# w550io_Teensy_DMX.net
KiCad netlist of a schematic drawn in EAGLE
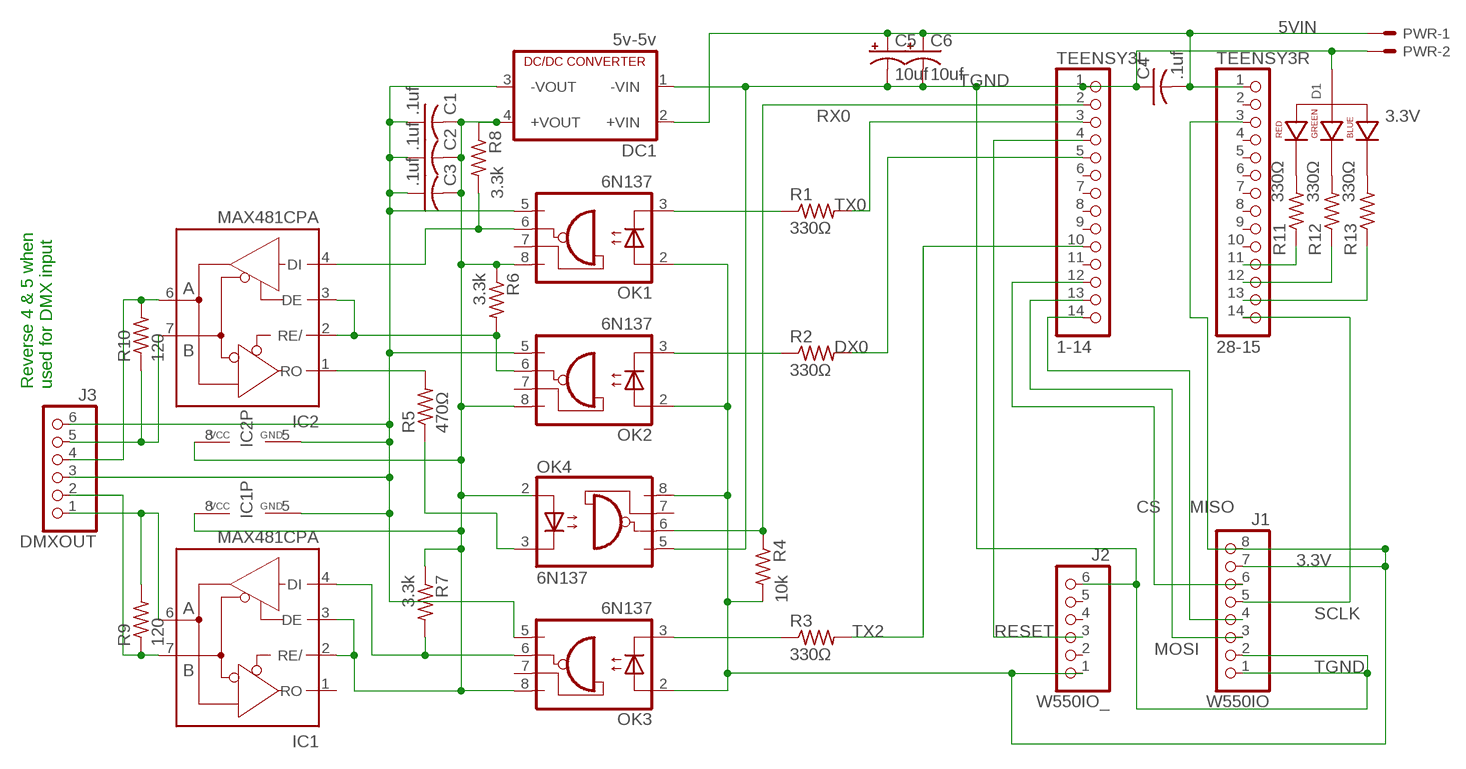
[diagram p0: schematic, sheet 1]

(export (version "E")
  (design (tool "Eeschema 10.0.6"))
  (components
    (comp (ref "C1")
      (value ".1uf")
      (footprint "eagle-import:C050-024X044")
      (libsource (lib "eagle-import") (part "C-US050-024X044"))
    )
    (comp (ref "C2")
      (value ".1uf")
      (footprint "eagle-import:C050-024X044")
      (libsource (lib "eagle-import") (part "C-US050-024X044"))
    )
    (comp (ref "C3")
      (value ".1uf")
      (footprint "eagle-import:C050-024X044")
      (libsource (lib "eagle-import") (part "C-US050-024X044"))
    )
    (comp (ref "C4")
      (value ".1uf")
      (footprint "eagle-import:C050-024X044")
      (libsource (lib "eagle-import") (part "C-US050-024X044"))
    )
    (comp (ref "C5")
      (value "10uf")
      (footprint "eagle-import:B45181B")
      (libsource (lib "eagle-import") (part "CPOL-USB45181B"))
    )
    (comp (ref "C6")
      (value "10uf")
      (footprint "eagle-import:B45181B")
      (libsource (lib "eagle-import") (part "CPOL-USB45181B"))
    )
    (comp (ref "D1")
      (value "LED-RGB-CA-THRUCLEAR")
      (footprint "eagle-import:LED-RGB-THRU")
      (libsource (lib "eagle-import") (part "LED-RGB-CA-THRUCLEAR"))
    )
    (comp (ref "DC1")
      (value "5v-5v")
      (footprint "eagle-import:NME")
      (fields (field (name "MF") "C & D TECHNOLOGIES, INC") (field (name "MPN") "NME1205D"))
      (libsource (lib "eagle-import") (part "NME"))
    )
    (comp (ref "DMXOUT")
      (value "J3")
      (footprint "eagle-import:1X06-BIG")
      (libsource (lib "eagle-import") (part "PINHD-1X6B"))
    )
    (comp (ref "IC1")
      (value "MAX481CPA")
      (footprint "eagle-import:DIL08")
      (fields (field (name "MPN") "MAX481CPA+"))
      (libsource (lib "eagle-import") (part "MAX481CPA"))
    )
    (comp (ref "IC2")
      (value "MAX481CPA")
      (footprint "eagle-import:DIL08")
      (fields (field (name "MPN") "MAX481CPA+"))
      (libsource (lib "eagle-import") (part "MAX481CPA"))
    )
    (comp (ref "OK1")
      (value "6N137")
      (footprint "eagle-import:DIL08")
      (libsource (lib "eagle-import") (part "6N137"))
    )
    (comp (ref "OK2")
      (value "6N137")
      (footprint "eagle-import:DIL08")
      (libsource (lib "eagle-import") (part "6N137"))
    )
    (comp (ref "OK3")
      (value "6N137")
      (footprint "eagle-import:DIL08")
      (libsource (lib "eagle-import") (part "6N137"))
    )
    (comp (ref "OK4")
      (value "6N137")
      (footprint "eagle-import:DIL08")
      (libsource (lib "eagle-import") (part "6N137"))
    )
    (comp (ref "PWR")
      (value "22-23-2021")
      (footprint "eagle-import:22-23-2021")
      (fields (field (name "MF") "MOLEX"))
      (libsource (lib "eagle-import") (part "22-23-2021"))
    )
    (comp (ref "R1")
      (value "330Ω")
      (footprint "eagle-import:0204_5")
      (libsource (lib "eagle-import") (part "R-US_0204/5"))
    )
    (comp (ref "R2")
      (value "330Ω")
      (footprint "eagle-import:0204_5")
      (libsource (lib "eagle-import") (part "R-US_0204/5"))
    )
    (comp (ref "R3")
      (value "330Ω")
      (footprint "eagle-import:0204_5")
      (libsource (lib "eagle-import") (part "R-US_0204/5"))
    )
    (comp (ref "R4")
      (value "10k")
      (footprint "eagle-import:0204_5")
      (libsource (lib "eagle-import") (part "R-US_0204/5"))
    )
    (comp (ref "R5")
      (value "470Ω")
      (footprint "eagle-import:0204_5")
      (libsource (lib "eagle-import") (part "R-US_0204/5"))
    )
    (comp (ref "R6")
      (value "3.3k")
      (footprint "eagle-import:0204_5")
      (libsource (lib "eagle-import") (part "R-US_0204/5"))
    )
    (comp (ref "R7")
      (value "3.3k")
      (footprint "eagle-import:0204_5")
      (libsource (lib "eagle-import") (part "R-US_0204/5"))
    )
    (comp (ref "R8")
      (value "3.3k")
      (footprint "eagle-import:0204_5")
      (libsource (lib "eagle-import") (part "R-US_0204/5"))
    )
    (comp (ref "R9")
      (value "120")
      (footprint "eagle-import:0204_5")
      (libsource (lib "eagle-import") (part "R-US_0204/5"))
    )
    (comp (ref "R10")
      (value "120")
      (footprint "eagle-import:0204_5")
      (libsource (lib "eagle-import") (part "R-US_0204/5"))
    )
    (comp (ref "R11")
      (value "330Ω")
      (footprint "eagle-import:0204_5")
      (libsource (lib "eagle-import") (part "R-US_0204/5"))
    )
    (comp (ref "R12")
      (value "330Ω")
      (footprint "eagle-import:0204_5")
      (libsource (lib "eagle-import") (part "R-US_0204/5"))
    )
    (comp (ref "R13")
      (value "330Ω")
      (footprint "eagle-import:0204_5")
      (libsource (lib "eagle-import") (part "R-US_0204/5"))
    )
    (comp (ref "TEENSY3L")
      (value "1-14")
      (footprint "eagle-import:1X14")
      (libsource (lib "eagle-import") (part "PINHD-1X14"))
    )
    (comp (ref "TEENSY3R")
      (value "28-15")
      (footprint "eagle-import:1X14")
      (libsource (lib "eagle-import") (part "PINHD-1X14"))
    )
    (comp (ref "W550IO")
      (value "J1")
      (footprint "eagle-import:1X08-BIG")
      (libsource (lib "eagle-import") (part "PINHD-1X8BIG"))
    )
    (comp (ref "W550IO_")
      (value "J2")
      (footprint "eagle-import:1X06-BIG")
      (libsource (lib "eagle-import") (part "PINHD-1X6B"))
    )
  )
  (nets
    (net (code "1") (name "/3.3V") (class "Default")
      (node (ref "OK1") (pin "2") (pinfunction "A_2") (pintype "passive"))
      (node (ref "OK2") (pin "2") (pinfunction "A_2") (pintype "passive"))
      (node (ref "OK3") (pin "2") (pinfunction "A_2") (pintype "passive"))
      (node (ref "OK4") (pin "8") (pinfunction "VCC_8") (pintype "passive"))
      (node (ref "R4") (pin "2") (pinfunction "2_2") (pintype "passive"))
      (node (ref "TEENSY3R") (pin "3") (pinfunction "3_3") (pintype "passive"))
      (node (ref "W550IO") (pin "7") (pinfunction "7_7") (pintype "passive"))
      (node (ref "W550IO") (pin "8") (pinfunction "8_8") (pintype "passive"))
      (node (ref "W550IO_") (pin "1") (pinfunction "1_1") (pintype "passive"))
    )
    (net (code "2") (name "/5VIN") (class "Default")
      (node (ref "C4") (pin "2") (pinfunction "2_2") (pintype "passive"))
      (node (ref "C5") (pin "+") (pinfunction "+_+") (pintype "passive"))
      (node (ref "C6") (pin "+") (pinfunction "+_+") (pintype "passive"))
      (node (ref "DC1") (pin "2") (pinfunction "+VIN_2") (pintype "passive"))
      (node (ref "PWR") (pin "1") (pinfunction "S_1") (pintype "passive"))
      (node (ref "TEENSY3R") (pin "1") (pinfunction "1_1") (pintype "passive"))
    )
    (net (code "3") (name "/CS") (class "Default")
      (node (ref "TEENSY3L") (pin "12") (pinfunction "12_12") (pintype "passive"))
      (node (ref "W550IO") (pin "6") (pinfunction "6_6") (pintype "passive"))
    )
    (net (code "4") (name "/DX0") (class "Default")
      (node (ref "R2") (pin "2") (pinfunction "2_2") (pintype "passive"))
      (node (ref "TEENSY3L") (pin "5") (pinfunction "5_5") (pintype "passive"))
    )
    (net (code "5") (name "/MISO") (class "Default")
      (node (ref "TEENSY3L") (pin "14") (pinfunction "14_14") (pintype "passive"))
      (node (ref "W550IO") (pin "4") (pinfunction "4_4") (pintype "passive"))
    )
    (net (code "6") (name "/MOSI") (class "Default")
      (node (ref "TEENSY3L") (pin "13") (pinfunction "13_13") (pintype "passive"))
      (node (ref "W550IO") (pin "3") (pinfunction "3_3") (pintype "passive"))
    )
    (net (code "7") (name "/RESET") (class "Default")
      (node (ref "TEENSY3L") (pin "4") (pinfunction "4_4") (pintype "passive"))
      (node (ref "W550IO_") (pin "3") (pinfunction "3_3") (pintype "passive"))
    )
    (net (code "8") (name "/RX0") (class "Default")
      (node (ref "OK4") (pin "6") (pinfunction "VO_6") (pintype "passive"))
      (node (ref "R4") (pin "1") (pinfunction "1_1") (pintype "passive"))
      (node (ref "TEENSY3L") (pin "2") (pinfunction "2_2") (pintype "passive"))
    )
    (net (code "9") (name "/SCLK") (class "Default")
      (node (ref "TEENSY3R") (pin "14") (pinfunction "14_14") (pintype "passive"))
      (node (ref "W550IO") (pin "5") (pinfunction "5_5") (pintype "passive"))
    )
    (net (code "10") (name "/TGND") (class "Default")
      (node (ref "C4") (pin "1") (pinfunction "1_1") (pintype "passive"))
      (node (ref "C5") (pin "-") (pinfunction "-_-") (pintype "passive"))
      (node (ref "C6") (pin "-") (pinfunction "-_-") (pintype "passive"))
      (node (ref "D1") (pin "2") (pinfunction "ANODE_2") (pintype "bidirectional"))
      (node (ref "DC1") (pin "1") (pinfunction "-VIN_1") (pintype "passive"))
      (node (ref "OK4") (pin "5") (pinfunction "GND_5") (pintype "passive"))
      (node (ref "PWR") (pin "2") (pinfunction "S_2") (pintype "passive"))
      (node (ref "TEENSY3L") (pin "1") (pinfunction "1_1") (pintype "passive"))
      (node (ref "W550IO") (pin "1") (pinfunction "1_1") (pintype "passive"))
      (node (ref "W550IO") (pin "2") (pinfunction "2_2") (pintype "passive"))
      (node (ref "W550IO_") (pin "6") (pinfunction "6_6") (pintype "passive"))
    )
    (net (code "11") (name "/TX0") (class "Default")
      (node (ref "R1") (pin "2") (pinfunction "2_2") (pintype "passive"))
      (node (ref "TEENSY3L") (pin "3") (pinfunction "3_3") (pintype "passive"))
    )
    (net (code "12") (name "/TX2") (class "Default")
      (node (ref "R3") (pin "2") (pinfunction "2_2") (pintype "passive"))
      (node (ref "TEENSY3L") (pin "10") (pinfunction "10_10") (pintype "passive"))
    )
    (net (code "13") (name "Net-(D1-BLUE_CATHODE)") (class "Default")
      (node (ref "D1") (pin "4") (pinfunction "BLUE_CATHODE_4") (pintype "bidirectional"))
      (node (ref "R13") (pin "2") (pinfunction "2_2") (pintype "passive"))
    )
    (net (code "14") (name "Net-(D1-GREEN_CATHODE)") (class "Default")
      (node (ref "D1") (pin "3") (pinfunction "GREEN_CATHODE_3") (pintype "bidirectional"))
      (node (ref "R12") (pin "2") (pinfunction "2_2") (pintype "passive"))
    )
    (net (code "15") (name "Net-(D1-RED_CATHODE)") (class "Default")
      (node (ref "D1") (pin "1") (pinfunction "RED_CATHODE_1") (pintype "bidirectional"))
      (node (ref "R11") (pin "2") (pinfunction "2_2") (pintype "passive"))
    )
    (net (code "16") (name "Net-(DC1-+VOUT)") (class "Default")
      (node (ref "C1") (pin "2") (pinfunction "2_2") (pintype "passive"))
      (node (ref "C2") (pin "2") (pinfunction "2_2") (pintype "passive"))
      (node (ref "C3") (pin "2") (pinfunction "2_2") (pintype "passive"))
      (node (ref "DC1") (pin "4") (pinfunction "+VOUT_4") (pintype "passive"))
      (node (ref "IC1") (pin "2") (pinfunction "RE/_2") (pintype "input"))
      (node (ref "IC1") (pin "3") (pinfunction "DE_3") (pintype "input"))
      (node (ref "IC1") (pin "8") (pinfunction "VCC_8") (pintype "power_in"))
      (node (ref "IC2") (pin "8") (pinfunction "VCC_8") (pintype "power_in"))
      (node (ref "OK1") (pin "8") (pinfunction "VCC_8") (pintype "passive"))
      (node (ref "OK2") (pin "8") (pinfunction "VCC_8") (pintype "passive"))
      (node (ref "OK3") (pin "8") (pinfunction "VCC_8") (pintype "passive"))
      (node (ref "OK4") (pin "2") (pinfunction "A_2") (pintype "passive"))
      (node (ref "R6") (pin "1") (pinfunction "1_1") (pintype "passive"))
      (node (ref "R7") (pin "1") (pinfunction "1_1") (pintype "passive"))
      (node (ref "R8") (pin "1") (pinfunction "1_1") (pintype "passive"))
    )
    (net (code "17") (name "Net-(DC1--VOUT)") (class "Default")
      (node (ref "C1") (pin "1") (pinfunction "1_1") (pintype "passive"))
      (node (ref "C2") (pin "1") (pinfunction "1_1") (pintype "passive"))
      (node (ref "C3") (pin "1") (pinfunction "1_1") (pintype "passive"))
      (node (ref "DC1") (pin "3") (pinfunction "-VOUT_3") (pintype "passive"))
      (node (ref "DMXOUT") (pin "3") (pinfunction "3_3") (pintype "passive"))
      (node (ref "DMXOUT") (pin "6") (pinfunction "6_6") (pintype "passive"))
      (node (ref "IC1") (pin "5") (pinfunction "GND_5") (pintype "power_in"))
      (node (ref "IC2") (pin "5") (pinfunction "GND_5") (pintype "power_in"))
      (node (ref "OK1") (pin "5") (pinfunction "GND_5") (pintype "passive"))
      (node (ref "OK2") (pin "5") (pinfunction "GND_5") (pintype "passive"))
      (node (ref "OK3") (pin "5") (pinfunction "GND_5") (pintype "passive"))
    )
    (net (code "18") (name "Net-(IC1A-A)") (class "Default")
      (node (ref "DMXOUT") (pin "1") (pinfunction "1_1") (pintype "passive"))
      (node (ref "IC1") (pin "6") (pinfunction "A_6") (pintype "passive"))
      (node (ref "R9") (pin "2") (pinfunction "2_2") (pintype "passive"))
    )
    (net (code "19") (name "Net-(IC1A-B)") (class "Default")
      (node (ref "DMXOUT") (pin "2") (pinfunction "2_2") (pintype "passive"))
      (node (ref "IC1") (pin "7") (pinfunction "B_7") (pintype "passive"))
      (node (ref "R9") (pin "1") (pinfunction "1_1") (pintype "passive"))
    )
    (net (code "20") (name "Net-(IC1A-DI)") (class "Default")
      (node (ref "IC1") (pin "4") (pinfunction "DI_4") (pintype "input"))
      (node (ref "OK3") (pin "6") (pinfunction "VO_6") (pintype "passive"))
      (node (ref "R7") (pin "2") (pinfunction "2_2") (pintype "passive"))
    )
    (net (code "21") (name "Net-(IC2A-A)") (class "Default")
      (node (ref "DMXOUT") (pin "4") (pinfunction "4_4") (pintype "passive"))
      (node (ref "IC2") (pin "6") (pinfunction "A_6") (pintype "passive"))
      (node (ref "R10") (pin "2") (pinfunction "2_2") (pintype "passive"))
    )
    (net (code "22") (name "Net-(IC2A-B)") (class "Default")
      (node (ref "DMXOUT") (pin "5") (pinfunction "5_5") (pintype "passive"))
      (node (ref "IC2") (pin "7") (pinfunction "B_7") (pintype "passive"))
      (node (ref "R10") (pin "1") (pinfunction "1_1") (pintype "passive"))
    )
    (net (code "23") (name "Net-(IC2A-DE)") (class "Default")
      (node (ref "IC2") (pin "2") (pinfunction "RE/_2") (pintype "input"))
      (node (ref "IC2") (pin "3") (pinfunction "DE_3") (pintype "input"))
      (node (ref "OK2") (pin "6") (pinfunction "VO_6") (pintype "passive"))
      (node (ref "R6") (pin "2") (pinfunction "2_2") (pintype "passive"))
    )
    (net (code "24") (name "Net-(IC2A-DI)") (class "Default")
      (node (ref "IC2") (pin "4") (pinfunction "DI_4") (pintype "input"))
      (node (ref "OK1") (pin "6") (pinfunction "VO_6") (pintype "passive"))
      (node (ref "R8") (pin "2") (pinfunction "2_2") (pintype "passive"))
    )
    (net (code "25") (name "Net-(IC2A-RO)") (class "Default")
      (node (ref "IC2") (pin "1") (pinfunction "RO_1") (pintype "output"))
      (node (ref "R5") (pin "2") (pinfunction "2_2") (pintype "passive"))
    )
    (net (code "26") (name "Net-(OK1-C)") (class "Default")
      (node (ref "OK1") (pin "3") (pinfunction "C_3") (pintype "passive"))
      (node (ref "R1") (pin "1") (pinfunction "1_1") (pintype "passive"))
    )
    (net (code "27") (name "Net-(OK2-C)") (class "Default")
      (node (ref "OK2") (pin "3") (pinfunction "C_3") (pintype "passive"))
      (node (ref "R2") (pin "1") (pinfunction "1_1") (pintype "passive"))
    )
    (net (code "28") (name "Net-(OK3-C)") (class "Default")
      (node (ref "OK3") (pin "3") (pinfunction "C_3") (pintype "passive"))
      (node (ref "R3") (pin "1") (pinfunction "1_1") (pintype "passive"))
    )
    (net (code "29") (name "Net-(OK4-C)") (class "Default")
      (node (ref "OK4") (pin "3") (pinfunction "C_3") (pintype "passive"))
      (node (ref "R5") (pin "1") (pinfunction "1_1") (pintype "passive"))
    )
    (net (code "30") (name "Net-(R11-Pad1)") (class "Default")
      (node (ref "R11") (pin "1") (pinfunction "1_1") (pintype "passive"))
      (node (ref "TEENSY3R") (pin "11") (pinfunction "11_11") (pintype "passive"))
    )
    (net (code "31") (name "Net-(R12-Pad1)") (class "Default")
      (node (ref "R12") (pin "1") (pinfunction "1_1") (pintype "passive"))
      (node (ref "TEENSY3R") (pin "12") (pinfunction "12_12") (pintype "passive"))
    )
    (net (code "32") (name "Net-(R13-Pad1)") (class "Default")
      (node (ref "R13") (pin "1") (pinfunction "1_1") (pintype "passive"))
      (node (ref "TEENSY3R") (pin "13") (pinfunction "13_13") (pintype "passive"))
    )
    (net (code "33") (name "unconnected-(IC1A-RO-Pad1)") (class "Default")
      (node (ref "IC1") (pin "1") (pinfunction "RO_1") (pintype "output"))
    )
    (net (code "34") (name "unconnected-(OK1-VE-Pad7)") (class "Default")
      (node (ref "OK1") (pin "7") (pinfunction "VE_7") (pintype "passive"))
    )
    (net (code "35") (name "unconnected-(OK2-VE-Pad7)") (class "Default")
      (node (ref "OK2") (pin "7") (pinfunction "VE_7") (pintype "passive"))
    )
    (net (code "36") (name "unconnected-(OK3-VE-Pad7)") (class "Default")
      (node (ref "OK3") (pin "7") (pinfunction "VE_7") (pintype "passive"))
    )
    (net (code "37") (name "unconnected-(OK4-VE-Pad7)") (class "Default")
      (node (ref "OK4") (pin "7") (pinfunction "VE_7") (pintype "passive"))
    )
    (net (code "38") (name "unconnected-(TEENSY3L-Pad6)") (class "Default")
      (node (ref "TEENSY3L") (pin "6") (pinfunction "6_6") (pintype "passive"))
    )
    (net (code "39") (name "unconnected-(TEENSY3L-Pad7)") (class "Default")
      (node (ref "TEENSY3L") (pin "7") (pinfunction "7_7") (pintype "passive"))
    )
    (net (code "40") (name "unconnected-(TEENSY3L-Pad8)") (class "Default")
      (node (ref "TEENSY3L") (pin "8") (pinfunction "8_8") (pintype "passive"))
    )
    (net (code "41") (name "unconnected-(TEENSY3L-Pad9)") (class "Default")
      (node (ref "TEENSY3L") (pin "9") (pinfunction "9_9") (pintype "passive"))
    )
    (net (code "42") (name "unconnected-(TEENSY3L-Pad11)") (class "Default")
      (node (ref "TEENSY3L") (pin "11") (pinfunction "11_11") (pintype "passive"))
    )
    (net (code "43") (name "unconnected-(TEENSY3R-Pad2)") (class "Default")
      (node (ref "TEENSY3R") (pin "2") (pinfunction "2_2") (pintype "passive"))
    )
    (net (code "44") (name "unconnected-(TEENSY3R-Pad4)") (class "Default")
      (node (ref "TEENSY3R") (pin "4") (pinfunction "4_4") (pintype "passive"))
    )
    (net (code "45") (name "unconnected-(TEENSY3R-Pad5)") (class "Default")
      (node (ref "TEENSY3R") (pin "5") (pinfunction "5_5") (pintype "passive"))
    )
    (net (code "46") (name "unconnected-(TEENSY3R-Pad6)") (class "Default")
      (node (ref "TEENSY3R") (pin "6") (pinfunction "6_6") (pintype "passive"))
    )
    (net (code "47") (name "unconnected-(TEENSY3R-Pad7)") (class "Default")
      (node (ref "TEENSY3R") (pin "7") (pinfunction "7_7") (pintype "passive"))
    )
    (net (code "48") (name "unconnected-(TEENSY3R-Pad8)") (class "Default")
      (node (ref "TEENSY3R") (pin "8") (pinfunction "8_8") (pintype "passive"))
    )
    (net (code "49") (name "unconnected-(TEENSY3R-Pad9)") (class "Default")
      (node (ref "TEENSY3R") (pin "9") (pinfunction "9_9") (pintype "passive"))
    )
    (net (code "50") (name "unconnected-(TEENSY3R-Pad10)") (class "Default")
      (node (ref "TEENSY3R") (pin "10") (pinfunction "10_10") (pintype "passive"))
    )
    (net (code "51") (name "unconnected-(W550IO_-Pad2)") (class "Default")
      (node (ref "W550IO_") (pin "2") (pinfunction "2_2") (pintype "passive"))
    )
    (net (code "52") (name "unconnected-(W550IO_-Pad4)") (class "Default")
      (node (ref "W550IO_") (pin "4") (pinfunction "4_4") (pintype "passive"))
    )
    (net (code "53") (name "unconnected-(W550IO_-Pad5)") (class "Default")
      (node (ref "W550IO_") (pin "5") (pinfunction "5_5") (pintype "passive"))
    )
  )
)
